# e-stim.net
KiCad netlist of a schematic drawn in Altium Designer
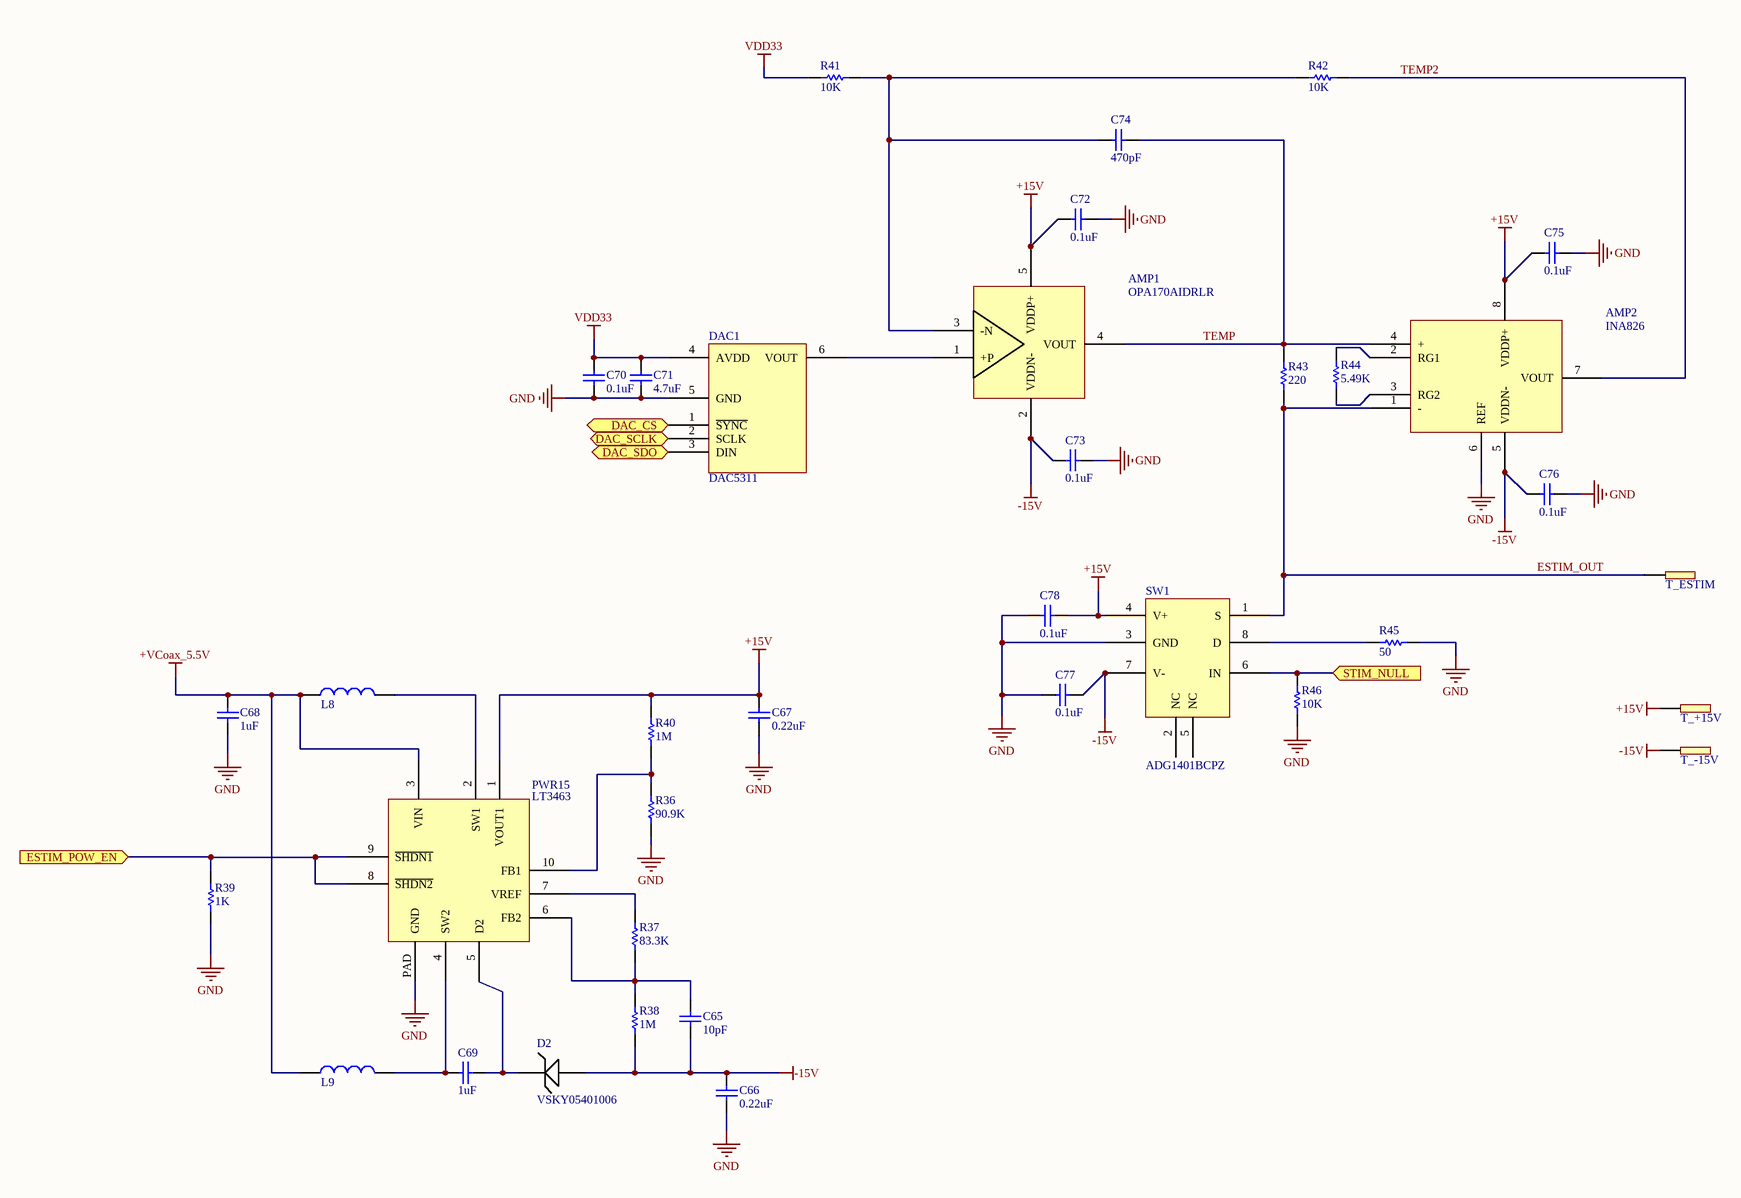
[diagram p0: e-stim.SchDoc]

(export (version "E")
  (design (tool "Eeschema 10.0.6"))
  (components
    (comp (ref "AMP1")
      (value "OPA170AIDRLR")
      (footprint "OPA170-DRL")
      (libsource (lib "Jack_SCH_Lib1") (part "OPA170AIDRLR"))
    )
    (comp (ref "AMP2")
      (value "INA826")
      (footprint "INA826AIDRGR")
      (libsource (lib "Jack_SCH_Lib1") (part "INA826"))
    )
    (comp (ref "C65")
      (value "10pF")
      (footprint "Cap-0603")
      (description "Capacitor")
      (fields (field (name "Comment") "X7R Ceramic") (field (name "PUBLISHER") "Altium Limited"))
      (libsource (lib "Miscellaneous Devices") (part "Cap"))
    )
    (comp (ref "C66")
      (value "0.22uF")
      (footprint "Cap-0603")
      (description "Capacitor")
      (fields (field (name "Comment") "X7R Ceramic") (field (name "PUBLISHER") "Altium Limited"))
      (libsource (lib "Miscellaneous Devices") (part "Cap"))
    )
    (comp (ref "C67")
      (value "0.22uF")
      (footprint "Cap-0603")
      (description "Capacitor")
      (fields (field (name "Comment") "X7R Ceramic") (field (name "PUBLISHER") "Altium Limited"))
      (libsource (lib "Miscellaneous Devices") (part "Cap"))
    )
    (comp (ref "C68")
      (value "1uF")
      (footprint "Cap-0603")
      (description "Capacitor")
      (fields (field (name "Comment") "X7R Ceramic") (field (name "PUBLISHER") "Altium Limited"))
      (libsource (lib "Miscellaneous Devices") (part "Cap"))
    )
    (comp (ref "C69")
      (value "1uF")
      (footprint "Cap-0603")
      (description "Capacitor")
      (fields (field (name "Comment") "X7R Ceramic") (field (name "PUBLISHER") "Altium Limited"))
      (libsource (lib "Miscellaneous Devices") (part "Cap"))
    )
    (comp (ref "C70")
      (value "0.1uF")
      (footprint "Cap_0402")
      (description "Capacitor")
      (fields (field (name "Comment") "X7R Ceramic") (field (name "PUBLISHER") "Altium Limited"))
      (libsource (lib "Miscellaneous Devices") (part "Cap"))
    )
    (comp (ref "C71")
      (value "4.7uF")
      (footprint "Cap_0402")
      (description "Capacitor")
      (fields (field (name "Comment") "X7R Ceramic") (field (name "PUBLISHER") "Altium Limited"))
      (libsource (lib "Miscellaneous Devices") (part "Cap"))
    )
    (comp (ref "C72")
      (value "0.1uF")
      (footprint "Cap_0402")
      (description "Capacitor")
      (fields (field (name "Comment") "X7R Ceramic") (field (name "PUBLISHER") "Altium Limited"))
      (libsource (lib "Miscellaneous Devices") (part "Cap"))
    )
    (comp (ref "C73")
      (value "0.1uF")
      (footprint "Cap_0402")
      (description "Capacitor")
      (fields (field (name "Comment") "X7R Ceramic") (field (name "PUBLISHER") "Altium Limited"))
      (libsource (lib "Miscellaneous Devices") (part "Cap"))
    )
    (comp (ref "C74")
      (value "470pF")
      (footprint "Cap_0402")
      (description "Capacitor")
      (fields (field (name "Comment") "X7R Ceramic") (field (name "PUBLISHER") "Altium Limited"))
      (libsource (lib "Miscellaneous Devices") (part "Cap"))
    )
    (comp (ref "C75")
      (value "0.1uF")
      (footprint "Cap_0402")
      (description "Capacitor")
      (fields (field (name "Comment") "X7R Ceramic") (field (name "PUBLISHER") "Altium Limited"))
      (libsource (lib "Miscellaneous Devices") (part "Cap"))
    )
    (comp (ref "C76")
      (value "0.1uF")
      (footprint "Cap_0402")
      (description "Capacitor")
      (fields (field (name "Comment") "X7R Ceramic") (field (name "PUBLISHER") "Altium Limited"))
      (libsource (lib "Miscellaneous Devices") (part "Cap"))
    )
    (comp (ref "C77")
      (value "0.1uF")
      (footprint "Cap_0402")
      (description "Capacitor")
      (fields (field (name "Comment") "X7R Ceramic") (field (name "PUBLISHER") "Altium Limited"))
      (libsource (lib "Miscellaneous Devices") (part "Cap"))
    )
    (comp (ref "C78")
      (value "0.1uF")
      (footprint "Cap_0402")
      (description "Capacitor")
      (fields (field (name "Comment") "X7R Ceramic") (field (name "PUBLISHER") "Altium Limited"))
      (libsource (lib "Miscellaneous Devices") (part "Cap"))
    )
    (comp (ref "D2")
      (value "VSKY05401006")
      (footprint "Cap_0402")
      (libsource (lib "Jack_SCH_Lib1") (part "VSKY05401006"))
    )
    (comp (ref "DAC1")
      (value "DAC5311")
      (footprint "DAC5311")
      (libsource (lib "Jack_SCH_Lib1") (part "DAC5311"))
    )
    (comp (ref "L8")
      (value "Ferrite Bead")
      (footprint "MLZ2012M100WT000")
      (libsource (lib "DA_Component_Library") (part "Ferrite Bead"))
    )
    (comp (ref "L9")
      (value "Ferrite Bead")
      (footprint "MLZ2012M100WT000")
      (libsource (lib "DA_Component_Library") (part "Ferrite Bead"))
    )
    (comp (ref "PWR15")
      (value "LT3463")
      (footprint "LT3463")
      (libsource (lib "Jack_SCH_Lib1") (part "LT3463"))
    )
    (comp (ref "R36")
      (value "90.9K")
      (footprint "Res_0402")
      (description "Resistor")
      (fields (field (name "Comment") "Res1") (field (name "PUBLISHER") "Altium Limited"))
      (libsource (lib "Miscellaneous Devices") (part "Res1"))
    )
    (comp (ref "R37")
      (value "83.3K")
      (footprint "Res_0402")
      (description "Resistor")
      (fields (field (name "Comment") "Res1") (field (name "PUBLISHER") "Altium Limited"))
      (libsource (lib "Miscellaneous Devices") (part "Res1"))
    )
    (comp (ref "R38")
      (value "1M")
      (footprint "Res_0402")
      (description "Resistor")
      (fields (field (name "Comment") "Res1") (field (name "PUBLISHER") "Altium Limited"))
      (libsource (lib "Miscellaneous Devices") (part "Res1"))
    )
    (comp (ref "R39")
      (value "1K")
      (footprint "Res_0402")
      (description "Resistor")
      (fields (field (name "Comment") "Res1") (field (name "PUBLISHER") "Altium Limited"))
      (libsource (lib "Miscellaneous Devices") (part "Res1"))
    )
    (comp (ref "R40")
      (value "1M")
      (footprint "Res_0402")
      (description "Resistor")
      (fields (field (name "Comment") "Res1") (field (name "PUBLISHER") "Altium Limited"))
      (libsource (lib "Miscellaneous Devices") (part "Res1"))
    )
    (comp (ref "R41")
      (value "10K")
      (footprint "Res_0402")
      (description "Resistor")
      (fields (field (name "Comment") "Res1") (field (name "PUBLISHER") "Altium Limited"))
      (libsource (lib "Miscellaneous Devices") (part "Res1"))
    )
    (comp (ref "R42")
      (value "10K")
      (footprint "Res_0402")
      (description "Resistor")
      (fields (field (name "Comment") "Res1") (field (name "PUBLISHER") "Altium Limited"))
      (libsource (lib "Miscellaneous Devices") (part "Res1"))
    )
    (comp (ref "R43")
      (value "220")
      (footprint "Res_0402")
      (description "Resistor")
      (fields (field (name "Comment") "Res1") (field (name "PUBLISHER") "Altium Limited"))
      (libsource (lib "Miscellaneous Devices") (part "Res1"))
    )
    (comp (ref "R44")
      (value "5.49K")
      (footprint "Res_0402")
      (description "Resistor")
      (fields (field (name "Comment") "Res1") (field (name "PUBLISHER") "Altium Limited"))
      (libsource (lib "Miscellaneous Devices") (part "Res1"))
    )
    (comp (ref "R45")
      (value "50")
      (footprint "Res_0402")
      (description "Resistor")
      (fields (field (name "Comment") "Res1") (field (name "PUBLISHER") "Altium Limited"))
      (libsource (lib "Miscellaneous Devices") (part "Res1"))
    )
    (comp (ref "R46")
      (value "10K")
      (footprint "Res_0402")
      (description "Resistor")
      (fields (field (name "Comment") "Res1") (field (name "PUBLISHER") "Altium Limited"))
      (libsource (lib "Miscellaneous Devices") (part "Res1"))
    )
    (comp (ref "SW1")
      (value "ADG1401BCPZ")
      (footprint "ADG1401BCPZ")
      (libsource (lib "Jack_SCH_Lib1") (part "ADG1401BCPZ"))
    )
    (comp (ref "T_+15V")
      (value "Header_1PIN")
      (footprint "JUMPER1PIN")
      (libsource (lib "Jack_SCH_Lib1") (part "Header_1PIN"))
    )
    (comp (ref "T_-15V")
      (value "Header_1PIN")
      (footprint "JUMPER1PIN")
      (libsource (lib "Jack_SCH_Lib1") (part "Header_1PIN"))
    )
    (comp (ref "T_ESTIM")
      (value "Header_1PIN")
      (footprint "JUMPER1PIN")
      (libsource (lib "Jack_SCH_Lib1") (part "Header_1PIN"))
    )
  )
  (nets
    (net (code "1") (name "+15V") (class "Default")
      (node (ref "AMP1") (pin "5") (pinfunction "VDDP+_5") (pintype "passive"))
      (node (ref "AMP2") (pin "8") (pinfunction "VDDP+_8") (pintype "passive"))
      (node (ref "C67") (pin "1") (pinfunction "1_1") (pintype "passive"))
      (node (ref "C72") (pin "1") (pinfunction "1_1") (pintype "passive"))
      (node (ref "C75") (pin "1") (pinfunction "1_1") (pintype "passive"))
      (node (ref "C78") (pin "2") (pinfunction "2_2") (pintype "passive"))
      (node (ref "PWR15") (pin "1") (pinfunction "VOUT1_1") (pintype "passive"))
      (node (ref "R40") (pin "2") (pinfunction "2_2") (pintype "passive"))
      (node (ref "SW1") (pin "4") (pinfunction "V+_4") (pintype "passive"))
      (node (ref "T_+15V") (pin "0") (pinfunction "0_0") (pintype "passive"))
    )
    (net (code "2") (name "+VCoax_5.5V") (class "Default")
      (node (ref "C68") (pin "1") (pinfunction "1_1") (pintype "passive"))
      (node (ref "L8") (pin "1") (pinfunction "1_1") (pintype "passive"))
      (node (ref "L9") (pin "1") (pinfunction "1_1") (pintype "passive"))
      (node (ref "PWR15") (pin "3") (pinfunction "VIN_3") (pintype "passive"))
    )
    (net (code "3") (name "-15V") (class "Default")
      (node (ref "AMP1") (pin "2") (pinfunction "VDDN-_2") (pintype "passive"))
      (node (ref "AMP2") (pin "5") (pinfunction "VDDN-_5") (pintype "passive"))
      (node (ref "C65") (pin "2") (pinfunction "2_2") (pintype "passive"))
      (node (ref "C66") (pin "1") (pinfunction "1_1") (pintype "passive"))
      (node (ref "C73") (pin "1") (pinfunction "1_1") (pintype "passive"))
      (node (ref "C76") (pin "1") (pinfunction "1_1") (pintype "passive"))
      (node (ref "C77") (pin "2") (pinfunction "2_2") (pintype "passive"))
      (node (ref "D2") (pin "2") (pinfunction "2_2") (pintype "passive"))
      (node (ref "R38") (pin "1") (pinfunction "1_1") (pintype "passive"))
      (node (ref "SW1") (pin "7") (pinfunction "V-_7") (pintype "passive"))
      (node (ref "T_-15V") (pin "0") (pinfunction "0_0") (pintype "passive"))
    )
    (net (code "4") (name "/DAC_CS") (class "Default")
      (node (ref "DAC1") (pin "1") (pinfunction "~{SYNC}_1") (pintype "passive"))
    )
    (net (code "5") (name "/DAC_SCLK") (class "Default")
      (node (ref "DAC1") (pin "2") (pinfunction "SCLK_2") (pintype "passive"))
    )
    (net (code "6") (name "/DAC_SDO") (class "Default")
      (node (ref "DAC1") (pin "3") (pinfunction "DIN_3") (pintype "passive"))
    )
    (net (code "7") (name "/ESTIM_OUT") (class "Default")
      (node (ref "AMP2") (pin "1") (pinfunction "-_1") (pintype "passive"))
      (node (ref "R43") (pin "2") (pinfunction "2_2") (pintype "passive"))
      (node (ref "SW1") (pin "1") (pinfunction "S_1") (pintype "passive"))
      (node (ref "T_ESTIM") (pin "0") (pinfunction "0_0") (pintype "passive"))
    )
    (net (code "8") (name "/ESTIM_POW_EN") (class "Default")
      (node (ref "PWR15") (pin "8") (pinfunction "~{SHDN2}_8") (pintype "passive"))
      (node (ref "PWR15") (pin "9") (pinfunction "~{SHDN1}_9") (pintype "passive"))
      (node (ref "R39") (pin "2") (pinfunction "2_2") (pintype "passive"))
    )
    (net (code "9") (name "/STIM_NULL") (class "Default")
      (node (ref "R46") (pin "2") (pinfunction "2_2") (pintype "passive"))
      (node (ref "SW1") (pin "6") (pinfunction "IN_6") (pintype "passive"))
    )
    (net (code "10") (name "/TEMP") (class "Default")
      (node (ref "AMP1") (pin "4") (pinfunction "VOUT_4") (pintype "passive"))
      (node (ref "AMP2") (pin "4") (pinfunction "+_4") (pintype "passive"))
      (node (ref "C74") (pin "2") (pinfunction "2_2") (pintype "passive"))
      (node (ref "R43") (pin "1") (pinfunction "1_1") (pintype "passive"))
    )
    (net (code "11") (name "/TEMP2") (class "Default")
      (node (ref "AMP2") (pin "7") (pinfunction "VOUT_7") (pintype "passive"))
      (node (ref "R42") (pin "1") (pinfunction "1_1") (pintype "passive"))
    )
    (net (code "12") (name "GND") (class "Default")
      (node (ref "AMP2") (pin "6") (pinfunction "REF_6") (pintype "passive"))
      (node (ref "C66") (pin "2") (pinfunction "2_2") (pintype "passive"))
      (node (ref "C67") (pin "2") (pinfunction "2_2") (pintype "passive"))
      (node (ref "C68") (pin "2") (pinfunction "2_2") (pintype "passive"))
      (node (ref "C70") (pin "2") (pinfunction "2_2") (pintype "passive"))
      (node (ref "C71") (pin "2") (pinfunction "2_2") (pintype "passive"))
      (node (ref "C72") (pin "2") (pinfunction "2_2") (pintype "passive"))
      (node (ref "C73") (pin "2") (pinfunction "2_2") (pintype "passive"))
      (node (ref "C75") (pin "2") (pinfunction "2_2") (pintype "passive"))
      (node (ref "C76") (pin "2") (pinfunction "2_2") (pintype "passive"))
      (node (ref "C77") (pin "1") (pinfunction "1_1") (pintype "passive"))
      (node (ref "C78") (pin "1") (pinfunction "1_1") (pintype "passive"))
      (node (ref "DAC1") (pin "5") (pinfunction "GND_5") (pintype "passive"))
      (node (ref "PWR15") (pin "PAD") (pinfunction "GND_PAD") (pintype "passive"))
      (node (ref "R36") (pin "1") (pinfunction "1_1") (pintype "passive"))
      (node (ref "R39") (pin "1") (pinfunction "1_1") (pintype "passive"))
      (node (ref "R45") (pin "2") (pinfunction "2_2") (pintype "passive"))
      (node (ref "R46") (pin "1") (pinfunction "1_1") (pintype "passive"))
      (node (ref "SW1") (pin "3") (pinfunction "GND_3") (pintype "passive"))
    )
    (net (code "13") (name "Net-(AMP1-+P)") (class "Default")
      (node (ref "AMP1") (pin "1") (pinfunction "+P_1") (pintype "passive"))
      (node (ref "DAC1") (pin "6") (pinfunction "VOUT_6") (pintype "passive"))
    )
    (net (code "14") (name "Net-(AMP1--N)") (class "Default")
      (node (ref "AMP1") (pin "3") (pinfunction "-N_3") (pintype "passive"))
      (node (ref "C74") (pin "1") (pinfunction "1_1") (pintype "passive"))
      (node (ref "R41") (pin "1") (pinfunction "1_1") (pintype "passive"))
      (node (ref "R42") (pin "2") (pinfunction "2_2") (pintype "passive"))
    )
    (net (code "15") (name "Net-(AMP2-RG1)") (class "Default")
      (node (ref "AMP2") (pin "2") (pinfunction "RG1_2") (pintype "passive"))
      (node (ref "R44") (pin "1") (pinfunction "1_1") (pintype "passive"))
    )
    (net (code "16") (name "Net-(AMP2-RG2)") (class "Default")
      (node (ref "AMP2") (pin "3") (pinfunction "RG2_3") (pintype "passive"))
      (node (ref "R44") (pin "2") (pinfunction "2_2") (pintype "passive"))
    )
    (net (code "17") (name "Net-(PWR15-D2)") (class "Default")
      (node (ref "C69") (pin "1") (pinfunction "1_1") (pintype "passive"))
      (node (ref "D2") (pin "1") (pinfunction "1_1") (pintype "passive"))
      (node (ref "PWR15") (pin "5") (pinfunction "D2_5") (pintype "passive"))
    )
    (net (code "18") (name "Net-(PWR15-FB1)") (class "Default")
      (node (ref "PWR15") (pin "10") (pinfunction "FB1_10") (pintype "passive"))
      (node (ref "R36") (pin "2") (pinfunction "2_2") (pintype "passive"))
      (node (ref "R40") (pin "1") (pinfunction "1_1") (pintype "passive"))
    )
    (net (code "19") (name "Net-(PWR15-FB2)") (class "Default")
      (node (ref "C65") (pin "1") (pinfunction "1_1") (pintype "passive"))
      (node (ref "PWR15") (pin "6") (pinfunction "FB2_6") (pintype "passive"))
      (node (ref "R37") (pin "1") (pinfunction "1_1") (pintype "passive"))
      (node (ref "R38") (pin "2") (pinfunction "2_2") (pintype "passive"))
    )
    (net (code "20") (name "Net-(PWR15-SW1)") (class "Default")
      (node (ref "L8") (pin "2") (pinfunction "2_2") (pintype "passive"))
      (node (ref "PWR15") (pin "2") (pinfunction "SW1_2") (pintype "passive"))
    )
    (net (code "21") (name "Net-(PWR15-SW2)") (class "Default")
      (node (ref "C69") (pin "2") (pinfunction "2_2") (pintype "passive"))
      (node (ref "L9") (pin "2") (pinfunction "2_2") (pintype "passive"))
      (node (ref "PWR15") (pin "4") (pinfunction "SW2_4") (pintype "passive"))
    )
    (net (code "22") (name "Net-(PWR15-VREF)") (class "Default")
      (node (ref "PWR15") (pin "7") (pinfunction "VREF_7") (pintype "passive"))
      (node (ref "R37") (pin "2") (pinfunction "2_2") (pintype "passive"))
    )
    (net (code "23") (name "Net-(SW1-D)") (class "Default")
      (node (ref "R45") (pin "1") (pinfunction "1_1") (pintype "passive"))
      (node (ref "SW1") (pin "8") (pinfunction "D_8") (pintype "passive"))
    )
    (net (code "24") (name "VDD33") (class "Default")
      (node (ref "C70") (pin "1") (pinfunction "1_1") (pintype "passive"))
      (node (ref "C71") (pin "1") (pinfunction "1_1") (pintype "passive"))
      (node (ref "DAC1") (pin "4") (pinfunction "AVDD_4") (pintype "passive"))
      (node (ref "R41") (pin "2") (pinfunction "2_2") (pintype "passive"))
    )
    (net (code "25") (name "unconnected-(SW1-NC-Pad2)") (class "Default")
      (node (ref "SW1") (pin "2") (pinfunction "NC_2") (pintype "passive"))
    )
    (net (code "26") (name "unconnected-(SW1-NC-Pad5)") (class "Default")
      (node (ref "SW1") (pin "5") (pinfunction "NC_5") (pintype "passive"))
    )
  )
)
